# AXAWIFIESP01.net
KiCad netlist of a schematic drawn in EAGLE
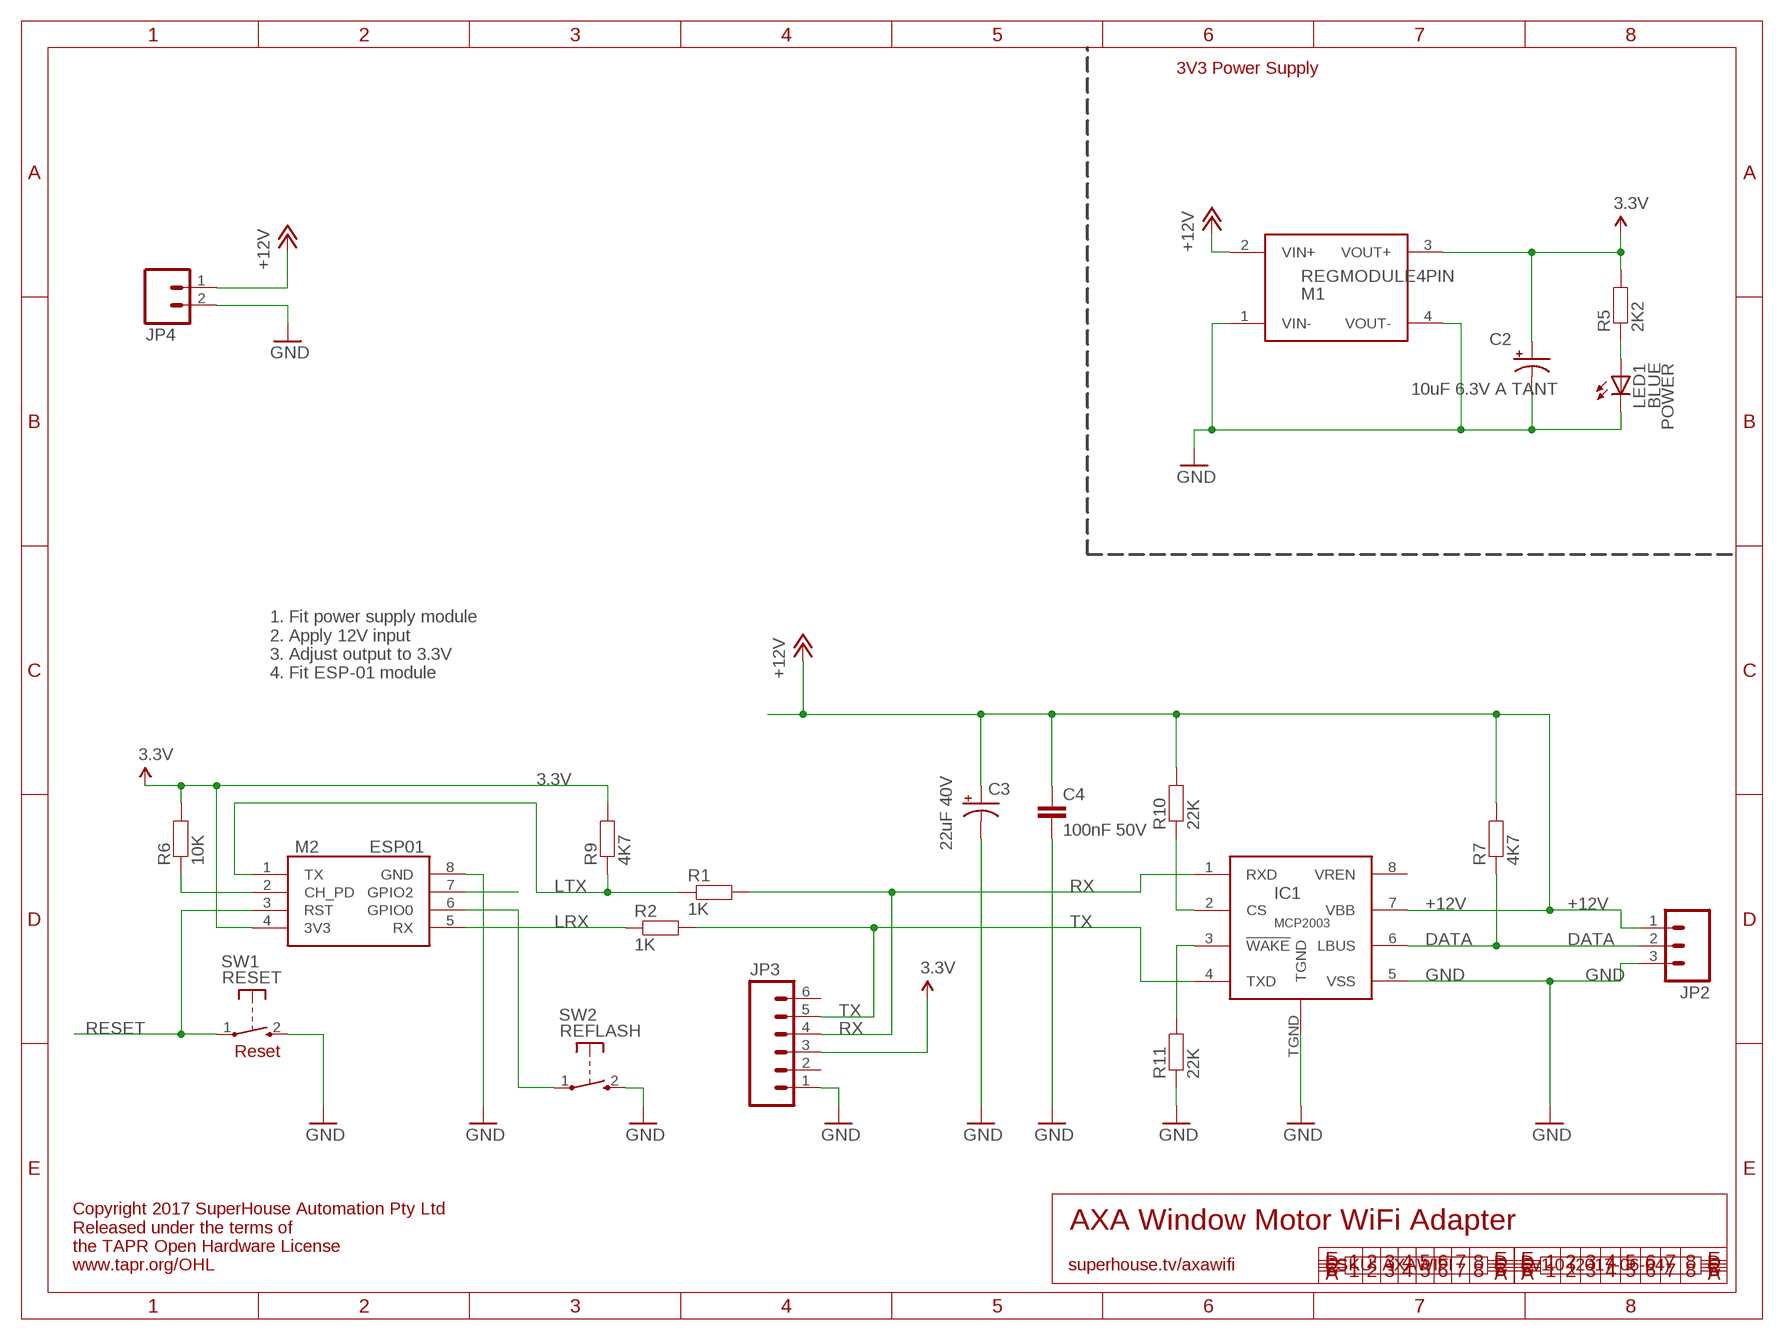
[diagram p0: schematic, sheet 1]

(export (version "E")
  (design (tool "Eeschema 10.0.6"))
  (components
    (comp (ref "C2")
      (value "10uF 6.3V A TANT")
      (footprint "eagle-import:EIA3216")
      (libsource (lib "eagle-import") (part "CAP_POL1206"))
    )
    (comp (ref "C3")
      (value "22uF 40V")
      (footprint "eagle-import:PANASONIC_C")
      (libsource (lib "eagle-import") (part "CAP_POLC"))
    )
    (comp (ref "C4")
      (value "100nF 50V")
      (footprint "eagle-import:C0603")
      (libsource (lib "eagle-import") (part "CAP0603"))
    )
    (comp (ref "IC1")
      (value "MCP2003")
      (footprint "eagle-import:SOIC8T")
      (libsource (lib "eagle-import") (part "MCP2003"))
    )
    (comp (ref "JP2")
      (value "M03PTH")
      (footprint "eagle-import:1X03")
      (libsource (lib "eagle-import") (part "M03PTH"))
    )
    (comp (ref "JP3")
      (value "M06SIP")
      (footprint "eagle-import:1X06")
      (libsource (lib "eagle-import") (part "M06SIP"))
    )
    (comp (ref "JP4")
      (value "M02-SCREW-3.5MM")
      (footprint "eagle-import:SCREWTERMINAL-3.5MM-2")
      (libsource (lib "eagle-import") (part "M02-SCREW-3.5MM"))
    )
    (comp (ref "LED1")
      (value "BLUE")
      (footprint "eagle-import:LED-0603")
      (libsource (lib "eagle-import") (part "LED0603"))
    )
    (comp (ref "M1")
      (value "REGMODULE4PIN")
      (footprint "eagle-import:REGMODULE4PIN")
      (libsource (lib "eagle-import") (part "REGMODULE4PIN"))
    )
    (comp (ref "M2")
      (value "ESP01")
      (footprint "eagle-import:ESP01")
      (libsource (lib "eagle-import") (part "ESP01"))
    )
    (comp (ref "R1")
      (value "1K")
      (footprint "eagle-import:R0603")
      (libsource (lib "eagle-import") (part "RESISTOR0603"))
    )
    (comp (ref "R2")
      (value "1K")
      (footprint "eagle-import:R0603")
      (libsource (lib "eagle-import") (part "RESISTOR0603"))
    )
    (comp (ref "R5")
      (value "2K2")
      (footprint "eagle-import:R0603")
      (libsource (lib "eagle-import") (part "RESISTOR0603"))
    )
    (comp (ref "R6")
      (value "10K")
      (footprint "eagle-import:R0603")
      (libsource (lib "eagle-import") (part "RESISTOR0603"))
    )
    (comp (ref "R7")
      (value "4K7")
      (footprint "eagle-import:R0603")
      (libsource (lib "eagle-import") (part "RESISTOR0603"))
    )
    (comp (ref "R9")
      (value "4K7")
      (footprint "eagle-import:R0603")
      (libsource (lib "eagle-import") (part "RESISTOR0603"))
    )
    (comp (ref "R10")
      (value "22K")
      (footprint "eagle-import:R0603")
      (libsource (lib "eagle-import") (part "RESISTOR0603"))
    )
    (comp (ref "R11")
      (value "22K")
      (footprint "eagle-import:R0603")
      (libsource (lib "eagle-import") (part "RESISTOR0603"))
    )
    (comp (ref "SW1")
      (value "RESET")
      (footprint "eagle-import:TACTILE_SMT_3X4X2")
      (libsource (lib "eagle-import") (part "TAC_SWITCH_2PINSMT"))
    )
    (comp (ref "SW2")
      (value "REFLASH")
      (footprint "eagle-import:TACTILE_SMT_3X4X2")
      (libsource (lib "eagle-import") (part "TAC_SWITCH_2PINSMT"))
    )
  )
  (nets
    (net (code "1") (name "+12V") (class "Default")
      (node (ref "C3") (pin "+") (pinfunction "+_+") (pintype "passive"))
      (node (ref "C4") (pin "1") (pinfunction "1_1") (pintype "passive"))
      (node (ref "IC1") (pin "7") (pinfunction "VBB_7") (pintype "power_in"))
      (node (ref "JP2") (pin "1") (pinfunction "1_1") (pintype "passive"))
      (node (ref "JP4") (pin "1") (pinfunction "1_1") (pintype "passive"))
      (node (ref "M1") (pin "2") (pinfunction "VIN+_2") (pintype "power_in"))
      (node (ref "R10") (pin "2") (pinfunction "2_2") (pintype "passive"))
      (node (ref "R7") (pin "2") (pinfunction "2_2") (pintype "passive"))
    )
    (net (code "2") (name "/DATA") (class "Default")
      (node (ref "IC1") (pin "6") (pinfunction "LBUS_6") (pintype "bidirectional"))
      (node (ref "JP2") (pin "2") (pinfunction "2_2") (pintype "passive"))
      (node (ref "R7") (pin "1") (pinfunction "1_1") (pintype "passive"))
    )
    (net (code "3") (name "/LRX") (class "Default")
      (node (ref "M2") (pin "5") (pinfunction "RX_5") (pintype "bidirectional"))
      (node (ref "R2") (pin "1") (pinfunction "1_1") (pintype "passive"))
    )
    (net (code "4") (name "/LTX") (class "Default")
      (node (ref "M2") (pin "1") (pinfunction "TX_1") (pintype "bidirectional"))
      (node (ref "R1") (pin "1") (pinfunction "1_1") (pintype "passive"))
      (node (ref "R9") (pin "1") (pinfunction "1_1") (pintype "passive"))
    )
    (net (code "5") (name "/RESET") (class "Default")
      (node (ref "M2") (pin "3") (pinfunction "RST_3") (pintype "bidirectional"))
      (node (ref "SW1") (pin "1") (pinfunction "P_1") (pintype "passive"))
    )
    (net (code "6") (name "/RX") (class "Default")
      (node (ref "IC1") (pin "1") (pinfunction "RXD_1") (pintype "input"))
      (node (ref "JP3") (pin "4") (pinfunction "4_4") (pintype "passive"))
      (node (ref "R1") (pin "2") (pinfunction "2_2") (pintype "passive"))
    )
    (net (code "7") (name "/TX") (class "Default")
      (node (ref "IC1") (pin "4") (pinfunction "TXD_4") (pintype "output"))
      (node (ref "JP3") (pin "5") (pinfunction "5_5") (pintype "passive"))
      (node (ref "R2") (pin "2") (pinfunction "2_2") (pintype "passive"))
    )
    (net (code "8") (name "3.3V") (class "Default")
      (node (ref "C2") (pin "A") (pinfunction "+_A") (pintype "passive"))
      (node (ref "JP3") (pin "3") (pinfunction "3_3") (pintype "passive"))
      (node (ref "M1") (pin "3") (pinfunction "VOUT+_3") (pintype "bidirectional"))
      (node (ref "M2") (pin "4") (pinfunction "3V3_4") (pintype "bidirectional"))
      (node (ref "R5") (pin "2") (pinfunction "2_2") (pintype "passive"))
      (node (ref "R6") (pin "2") (pinfunction "2_2") (pintype "passive"))
      (node (ref "R9") (pin "2") (pinfunction "2_2") (pintype "passive"))
    )
    (net (code "9") (name "GND") (class "Default")
      (node (ref "C2") (pin "C") (pinfunction "-_C") (pintype "passive"))
      (node (ref "C3") (pin "-") (pinfunction "-_-") (pintype "passive"))
      (node (ref "C4") (pin "2") (pinfunction "2_2") (pintype "passive"))
      (node (ref "IC1") (pin "5") (pinfunction "VSS_5") (pintype "power_in"))
      (node (ref "IC1") (pin "TGND") (pinfunction "TGND_TGND") (pintype "power_in"))
      (node (ref "JP2") (pin "3") (pinfunction "3_3") (pintype "passive"))
      (node (ref "JP3") (pin "1") (pinfunction "1_1") (pintype "passive"))
      (node (ref "JP4") (pin "2") (pinfunction "2_2") (pintype "passive"))
      (node (ref "LED1") (pin "C") (pinfunction "C_C") (pintype "passive"))
      (node (ref "M1") (pin "1") (pinfunction "VIN-_1") (pintype "power_in"))
      (node (ref "M1") (pin "4") (pinfunction "VOUT-_4") (pintype "bidirectional"))
      (node (ref "M2") (pin "8") (pinfunction "GND_8") (pintype "bidirectional"))
      (node (ref "R11") (pin "1") (pinfunction "1_1") (pintype "passive"))
      (node (ref "SW1") (pin "2") (pinfunction "S_2") (pintype "passive"))
      (node (ref "SW2") (pin "2") (pinfunction "S_2") (pintype "passive"))
    )
    (net (code "10") (name "Net-(IC1-CS)") (class "Default")
      (node (ref "IC1") (pin "2") (pinfunction "CS_2") (pintype "input"))
      (node (ref "R10") (pin "1") (pinfunction "1_1") (pintype "passive"))
    )
    (net (code "11") (name "Net-(IC1-~{WAKE})") (class "Default")
      (node (ref "IC1") (pin "3") (pinfunction "~{WAKE}_3") (pintype "input"))
      (node (ref "R11") (pin "2") (pinfunction "2_2") (pintype "passive"))
    )
    (net (code "12") (name "Net-(LED1-PadA)") (class "Default")
      (node (ref "LED1") (pin "A") (pinfunction "A_A") (pintype "passive"))
      (node (ref "R5") (pin "1") (pinfunction "1_1") (pintype "passive"))
    )
    (net (code "13") (name "Net-(M2-CH_PD)") (class "Default")
      (node (ref "M2") (pin "2") (pinfunction "CH_PD_2") (pintype "bidirectional"))
      (node (ref "R6") (pin "1") (pinfunction "1_1") (pintype "passive"))
    )
    (net (code "14") (name "Net-(M2-GPIO0)") (class "Default")
      (node (ref "M2") (pin "6") (pinfunction "GPIO0_6") (pintype "bidirectional"))
      (node (ref "SW2") (pin "1") (pinfunction "P_1") (pintype "passive"))
    )
    (net (code "15") (name "unconnected-(IC1-VREN-Pad8)") (class "Default")
      (node (ref "IC1") (pin "8") (pinfunction "VREN_8") (pintype "output"))
    )
    (net (code "16") (name "unconnected-(JP3-Pad2)") (class "Default")
      (node (ref "JP3") (pin "2") (pinfunction "2_2") (pintype "passive"))
    )
    (net (code "17") (name "unconnected-(JP3-Pad6)") (class "Default")
      (node (ref "JP3") (pin "6") (pinfunction "6_6") (pintype "passive"))
    )
    (net (code "18") (name "unconnected-(M2-GPIO2-Pad7)") (class "Default")
      (node (ref "M2") (pin "7") (pinfunction "GPIO2_7") (pintype "bidirectional"))
    )
  )
)
